# usbtinyisp.net
KiCad netlist of a schematic drawn in Altium Designer
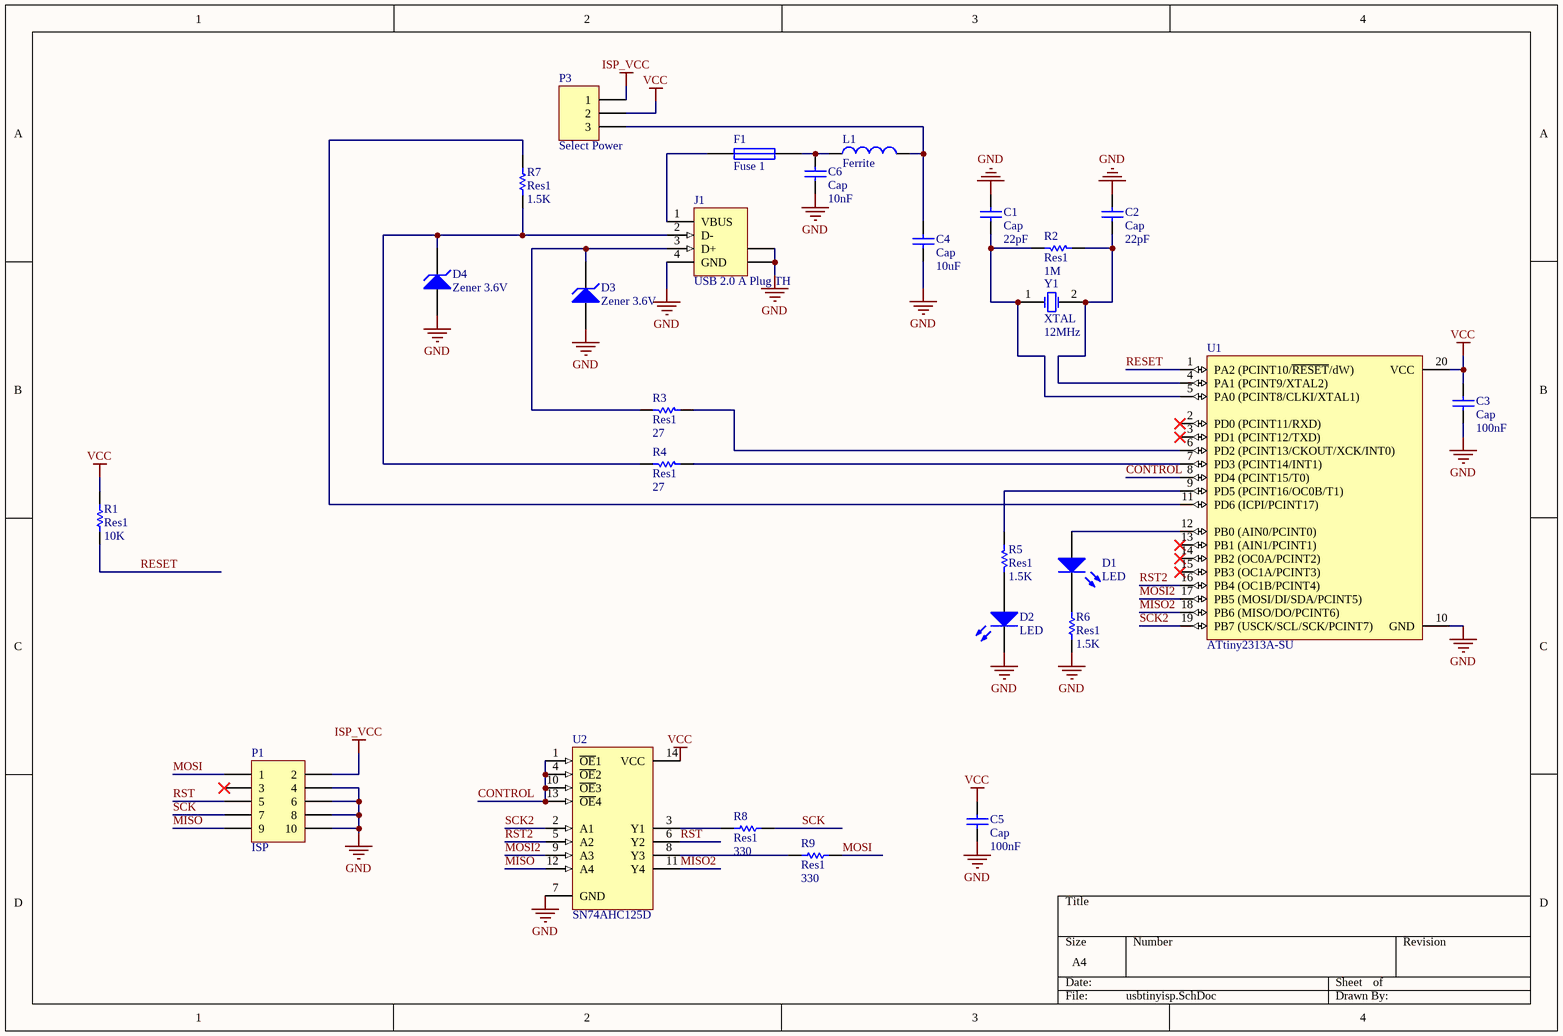
[diagram p0: usbtinyisp.SchDoc]

(export (version "E")
  (design (tool "Eeschema 10.0.6"))
  (components
    (comp (ref "C1")
      (value "Cap")
      (footprint "C0805")
      (description "Capacitor")
      (fields (field (name "ALTIUM_VALUE") "22pF") (field (name "PUBLISHER") "Altium Limited"))
      (libsource (lib "Miscellaneous Devices") (part "Cap"))
    )
    (comp (ref "C2")
      (value "Cap")
      (footprint "C0805")
      (description "Capacitor")
      (fields (field (name "ALTIUM_VALUE") "22pF") (field (name "PUBLISHER") "Altium Limited"))
      (libsource (lib "Miscellaneous Devices") (part "Cap"))
    )
    (comp (ref "C3")
      (value "Cap")
      (footprint "C0805")
      (description "Capacitor")
      (fields (field (name "ALTIUM_VALUE") "100nF") (field (name "PUBLISHER") "Altium Limited"))
      (libsource (lib "Miscellaneous Devices") (part "Cap"))
    )
    (comp (ref "C4")
      (value "Cap")
      (footprint "C0805")
      (description "Capacitor")
      (fields (field (name "ALTIUM_VALUE") "10uF") (field (name "PUBLISHER") "Altium Limited"))
      (libsource (lib "Miscellaneous Devices") (part "Cap"))
    )
    (comp (ref "C5")
      (value "Cap")
      (footprint "C0805")
      (description "Capacitor")
      (fields (field (name "ALTIUM_VALUE") "100nF") (field (name "PUBLISHER") "Altium Limited"))
      (libsource (lib "Miscellaneous Devices") (part "Cap"))
    )
    (comp (ref "C6")
      (value "Cap")
      (footprint "C0805")
      (description "Capacitor")
      (fields (field (name "ALTIUM_VALUE") "10nF") (field (name "PUBLISHER") "Altium Limited"))
      (libsource (lib "Miscellaneous Devices") (part "Cap"))
    )
    (comp (ref "D1")
      (value "LED")
      (footprint "C0805")
      (description "Typical RED GaAs LED")
      (fields (field (name "DESIGNER") "Meysam Parvizi") (field (name "EMAIL") "meysam.parvizi.ir@gmail.com"))
      (libsource (lib "mp") (part "LED"))
    )
    (comp (ref "D2")
      (value "LED")
      (footprint "C0805")
      (description "Typical RED GaAs LED")
      (fields (field (name "DESIGNER") "Meysam Parvizi") (field (name "EMAIL") "meysam.parvizi.ir@gmail.com"))
      (libsource (lib "mp") (part "LED"))
    )
    (comp (ref "D3")
      (value "Zener 3.6V")
      (footprint "DO-35")
      (description "Zener Diode")
      (fields (field (name "PUBLISHER") "Altium Limited"))
      (libsource (lib "Miscellaneous Devices") (part "D Zener"))
    )
    (comp (ref "D4")
      (value "Zener 3.6V")
      (footprint "DO-35")
      (description "Zener Diode")
      (fields (field (name "PUBLISHER") "Altium Limited"))
      (libsource (lib "Miscellaneous Devices") (part "D Zener"))
    )
    (comp (ref "F1")
      (value "Fuse 1")
      (footprint "C0805")
      (description "Fuse")
      (fields (field (name "PUBLISHER") "Altium Limited"))
      (libsource (lib "Miscellaneous Devices") (part "Fuse 1"))
    )
    (comp (ref "J1")
      (value "USB 2.0 A Plug TH")
      (footprint "USB2_A_TH_PLUG")
      (description "USB 2.0 A Plug, Thru-Hole")
      (libsource (lib "mp") (part "USB 2.0 A Plug TH"))
    )
    (comp (ref "L1")
      (value "Ferrite")
      (footprint "C0805")
      (description "Inductor")
      (fields (field (name "PUBLISHER") "Altium Limited"))
      (libsource (lib "Miscellaneous Devices") (part "Inductor"))
    )
    (comp (ref "P1")
      (value "ISP")
      (footprint "BOX2X5_PCB_EDGE")
      (description "Box, 5-Pin, Dual row")
      (fields (field (name "DESIGNER") "Meysam Parvizi") (field (name "EMAIL") "meysam.parvizi.ir@gmail.com"))
      (libsource (lib "mp") (part "Box 5X2"))
    )
    (comp (ref "P3")
      (value "Select Power")
      (footprint "HDR1X3")
      (description "Header, 3-Pin")
      (fields (field (name "PUBLISHER") "Altium Limited"))
      (libsource (lib "Miscellaneous Connectors") (part "Header 3"))
    )
    (comp (ref "R1")
      (value "Res1")
      (footprint "C0805")
      (description "Resistor")
      (fields (field (name "ALTIUM_VALUE") "10K") (field (name "PUBLISHER") "Altium Limited"))
      (libsource (lib "Miscellaneous Devices") (part "Res1"))
    )
    (comp (ref "R2")
      (value "Res1")
      (footprint "C0805")
      (description "Resistor")
      (fields (field (name "ALTIUM_VALUE") "1M") (field (name "PUBLISHER") "Altium Limited"))
      (libsource (lib "Miscellaneous Devices") (part "Res1"))
    )
    (comp (ref "R3")
      (value "Res1")
      (footprint "C0805")
      (description "Resistor")
      (fields (field (name "ALTIUM_VALUE") "27") (field (name "PUBLISHER") "Altium Limited"))
      (libsource (lib "Miscellaneous Devices") (part "Res1"))
    )
    (comp (ref "R4")
      (value "Res1")
      (footprint "C0805")
      (description "Resistor")
      (fields (field (name "ALTIUM_VALUE") "27") (field (name "PUBLISHER") "Altium Limited"))
      (libsource (lib "Miscellaneous Devices") (part "Res1"))
    )
    (comp (ref "R5")
      (value "Res1")
      (footprint "C0805")
      (description "Resistor")
      (fields (field (name "ALTIUM_VALUE") "1.5K") (field (name "PUBLISHER") "Altium Limited"))
      (libsource (lib "Miscellaneous Devices") (part "Res1"))
    )
    (comp (ref "R6")
      (value "Res1")
      (footprint "C0805")
      (description "Resistor")
      (fields (field (name "ALTIUM_VALUE") "1.5K") (field (name "PUBLISHER") "Altium Limited"))
      (libsource (lib "Miscellaneous Devices") (part "Res1"))
    )
    (comp (ref "R7")
      (value "Res1")
      (footprint "C0805")
      (description "Resistor")
      (fields (field (name "ALTIUM_VALUE") "1.5K") (field (name "PUBLISHER") "Altium Limited"))
      (libsource (lib "Miscellaneous Devices") (part "Res1"))
    )
    (comp (ref "R8")
      (value "Res1")
      (footprint "C0805")
      (description "Resistor")
      (fields (field (name "ALTIUM_VALUE") "330") (field (name "PUBLISHER") "Altium Limited"))
      (libsource (lib "Miscellaneous Devices") (part "Res1"))
    )
    (comp (ref "R9")
      (value "Res1")
      (footprint "C0805")
      (description "Resistor")
      (fields (field (name "ALTIUM_VALUE") "330") (field (name "PUBLISHER") "Altium Limited"))
      (libsource (lib "Miscellaneous Devices") (part "Res1"))
    )
    (comp (ref "U1")
      (value "ATtiny2313A-SU")
      (footprint "20S_M")
      (fields (field (name "PUBLISHER") "Altium Limited"))
      (libsource (lib "Atmel Microcontroller 8-Bit tinyAVR") (part "ATtiny2313A-SU"))
    )
    (comp (ref "U2")
      (value "SN74AHC125D")
      (footprint "D014_M")
      (description "Quadruple Bus Buffer Gate with 3-State Outputs")
      (fields (field (name "PUBLISHER") "Altium Limited"))
      (libsource (lib "TI Logic Buffer Line Driver") (part "SN74AHC125D"))
    )
    (comp (ref "Y1")
      (value "XTAL")
      (footprint "XTAL")
      (description "Crystal Oscillator")
      (fields
        (field (name "ALTIUM_VALUE") "12MHz")
        (field (name "DESIGNER") "Meysam Parvizi")
        (field (name "EMAIL") "meysam.parvizi.ir@gmail.com")
      )
      (libsource (lib "mp") (part "XTAL"))
    )
  )
  (nets
    (net (code "1") (name "/CONTROL") (class "Default")
      (node (ref "U1") (pin "8") (pinfunction "PD4_(PCINT15/T0)_8") (pintype "bidirectional"))
      (node (ref "U2") (pin "1") (pinfunction "~{OE}1_1") (pintype "input"))
      (node (ref "U2") (pin "10") (pinfunction "~{OE}3_10") (pintype "input"))
      (node (ref "U2") (pin "13") (pinfunction "~{OE}4_13") (pintype "input"))
      (node (ref "U2") (pin "4") (pinfunction "~{OE}2_4") (pintype "input"))
    )
    (net (code "2") (name "/MISO") (class "Default")
      (node (ref "P1") (pin "9") (pinfunction "9_9") (pintype "passive"))
      (node (ref "U2") (pin "12") (pinfunction "A4_12") (pintype "input"))
    )
    (net (code "3") (name "/MISO2") (class "Default")
      (node (ref "U1") (pin "18") (pinfunction "PB6_(MISO/DO/PCINT6)_18") (pintype "bidirectional"))
      (node (ref "U2") (pin "11") (pinfunction "Y4_11") (pintype "tri_state"))
    )
    (net (code "4") (name "/MOSI") (class "Default")
      (node (ref "P1") (pin "1") (pinfunction "1_1") (pintype "passive"))
      (node (ref "R9") (pin "2") (pinfunction "2_2") (pintype "passive"))
    )
    (net (code "5") (name "/MOSI2") (class "Default")
      (node (ref "U1") (pin "17") (pinfunction "PB5_(MOSI/DI/SDA/PCINT5)_17") (pintype "bidirectional"))
      (node (ref "U2") (pin "9") (pinfunction "A3_9") (pintype "input"))
    )
    (net (code "6") (name "/RESET") (class "Default")
      (node (ref "R1") (pin "1") (pinfunction "1_1") (pintype "passive"))
      (node (ref "U1") (pin "1") (pinfunction "PA2_(PCINT10/~{RESET}/dW)_1") (pintype "bidirectional"))
    )
    (net (code "7") (name "/RST") (class "Default")
      (node (ref "P1") (pin "5") (pinfunction "5_5") (pintype "passive"))
      (node (ref "U2") (pin "6") (pinfunction "Y2_6") (pintype "tri_state"))
    )
    (net (code "8") (name "/RST2") (class "Default")
      (node (ref "U1") (pin "16") (pinfunction "PB4_(OC1B/PCINT4)_16") (pintype "bidirectional"))
      (node (ref "U2") (pin "5") (pinfunction "A2_5") (pintype "input"))
    )
    (net (code "9") (name "/SCK") (class "Default")
      (node (ref "P1") (pin "7") (pinfunction "7_7") (pintype "passive"))
      (node (ref "R8") (pin "2") (pinfunction "2_2") (pintype "passive"))
    )
    (net (code "10") (name "/SCK2") (class "Default")
      (node (ref "U1") (pin "19") (pinfunction "PB7_(USCK/SCL/SCK/PCINT7)_19") (pintype "bidirectional"))
      (node (ref "U2") (pin "2") (pinfunction "A1_2") (pintype "input"))
    )
    (net (code "11") (name "GND") (class "Default")
      (node (ref "C1") (pin "1") (pinfunction "1_1") (pintype "passive"))
      (node (ref "C2") (pin "1") (pinfunction "1_1") (pintype "passive"))
      (node (ref "C3") (pin "1") (pinfunction "1_1") (pintype "passive"))
      (node (ref "C4") (pin "2") (pinfunction "2_2") (pintype "passive"))
      (node (ref "C5") (pin "1") (pinfunction "1_1") (pintype "passive"))
      (node (ref "C6") (pin "1") (pinfunction "1_1") (pintype "passive"))
      (node (ref "D2") (pin "2") (pinfunction "K_2") (pintype "passive"))
      (node (ref "D3") (pin "1") (pinfunction "A_1") (pintype "passive"))
      (node (ref "D4") (pin "1") (pinfunction "A_1") (pintype "passive"))
      (node (ref "J1") (pin "4") (pinfunction "GND_4") (pintype "power_in"))
      (node (ref "J1") (pin "5") (pinfunction "SHLD_5") (pintype "passive"))
      (node (ref "J1") (pin "6") (pinfunction "SHLD_6") (pintype "passive"))
      (node (ref "P1") (pin "10") (pinfunction "10_10") (pintype "passive"))
      (node (ref "P1") (pin "4") (pinfunction "4_4") (pintype "passive"))
      (node (ref "P1") (pin "6") (pinfunction "6_6") (pintype "passive"))
      (node (ref "P1") (pin "8") (pinfunction "8_8") (pintype "passive"))
      (node (ref "R6") (pin "2") (pinfunction "2_2") (pintype "passive"))
      (node (ref "U1") (pin "10") (pinfunction "GND_10") (pintype "power_in"))
      (node (ref "U2") (pin "7") (pinfunction "GND_7") (pintype "power_in"))
    )
    (net (code "12") (name "ISP_VCC") (class "Default")
      (node (ref "P1") (pin "2") (pinfunction "2_2") (pintype "passive"))
      (node (ref "P3") (pin "1") (pinfunction "1_1") (pintype "passive"))
    )
    (net (code "13") (name "Net-(C4-Pad1)") (class "Default")
      (node (ref "C4") (pin "1") (pinfunction "1_1") (pintype "passive"))
      (node (ref "L1") (pin "1") (pinfunction "1_1") (pintype "passive"))
      (node (ref "P3") (pin "3") (pinfunction "3_3") (pintype "passive"))
    )
    (net (code "14") (name "Net-(C6-Pad2)") (class "Default")
      (node (ref "C6") (pin "2") (pinfunction "2_2") (pintype "passive"))
      (node (ref "F1") (pin "1") (pinfunction "1_1") (pintype "passive"))
      (node (ref "L1") (pin "2") (pinfunction "2_2") (pintype "passive"))
    )
    (net (code "15") (name "Net-(D1-A)") (class "Default")
      (node (ref "D1") (pin "1") (pinfunction "A_1") (pintype "passive"))
      (node (ref "U1") (pin "12") (pinfunction "PB0_(AIN0/PCINT0)_12") (pintype "bidirectional"))
    )
    (net (code "16") (name "Net-(D1-K)") (class "Default")
      (node (ref "D1") (pin "2") (pinfunction "K_2") (pintype "passive"))
      (node (ref "R6") (pin "1") (pinfunction "1_1") (pintype "passive"))
    )
    (net (code "17") (name "Net-(D2-A)") (class "Default")
      (node (ref "D2") (pin "1") (pinfunction "A_1") (pintype "passive"))
      (node (ref "R5") (pin "2") (pinfunction "2_2") (pintype "passive"))
    )
    (net (code "18") (name "Net-(D3-K)") (class "Default")
      (node (ref "D3") (pin "2") (pinfunction "K_2") (pintype "passive"))
      (node (ref "J1") (pin "3") (pinfunction "D+_3") (pintype "input"))
      (node (ref "R3") (pin "1") (pinfunction "1_1") (pintype "passive"))
    )
    (net (code "19") (name "Net-(D4-K)") (class "Default")
      (node (ref "D4") (pin "2") (pinfunction "K_2") (pintype "passive"))
      (node (ref "J1") (pin "2") (pinfunction "D-_2") (pintype "input"))
      (node (ref "R4") (pin "1") (pinfunction "1_1") (pintype "passive"))
      (node (ref "R7") (pin "1") (pinfunction "1_1") (pintype "passive"))
    )
    (net (code "20") (name "Net-(J1-VBUS)") (class "Default")
      (node (ref "F1") (pin "2") (pinfunction "2_2") (pintype "passive"))
      (node (ref "J1") (pin "1") (pinfunction "VBUS_1") (pintype "power_in"))
    )
    (net (code "21") (name "Net-(U1-PA0_(PCINT8{slash}CLKI{slash}XTAL1))") (class "Default")
      (node (ref "C1") (pin "2") (pinfunction "2_2") (pintype "passive"))
      (node (ref "R2") (pin "2") (pinfunction "2_2") (pintype "passive"))
      (node (ref "U1") (pin "5") (pinfunction "PA0_(PCINT8/CLKI/XTAL1)_5") (pintype "bidirectional"))
      (node (ref "Y1") (pin "1") (pinfunction "OSC1_1") (pintype "passive"))
    )
    (net (code "22") (name "Net-(U1-PA1_(PCINT9{slash}XTAL2))") (class "Default")
      (node (ref "C2") (pin "2") (pinfunction "2_2") (pintype "passive"))
      (node (ref "R2") (pin "1") (pinfunction "1_1") (pintype "passive"))
      (node (ref "U1") (pin "4") (pinfunction "PA1_(PCINT9/XTAL2)_4") (pintype "bidirectional"))
      (node (ref "Y1") (pin "2") (pinfunction "OSC2_2") (pintype "passive"))
    )
    (net (code "23") (name "Net-(U1-PD2_(PCINT13{slash}CKOUT{slash}XCK{slash}INT0))") (class "Default")
      (node (ref "R3") (pin "2") (pinfunction "2_2") (pintype "passive"))
      (node (ref "U1") (pin "6") (pinfunction "PD2_(PCINT13/CKOUT/XCK/INT0)_6") (pintype "bidirectional"))
    )
    (net (code "24") (name "Net-(U1-PD3_(PCINT14{slash}INT1))") (class "Default")
      (node (ref "R4") (pin "2") (pinfunction "2_2") (pintype "passive"))
      (node (ref "U1") (pin "7") (pinfunction "PD3_(PCINT14/INT1)_7") (pintype "bidirectional"))
    )
    (net (code "25") (name "Net-(U1-PD5_(PCINT16{slash}OC0B{slash}T1))") (class "Default")
      (node (ref "R5") (pin "1") (pinfunction "1_1") (pintype "passive"))
      (node (ref "U1") (pin "9") (pinfunction "PD5_(PCINT16/OC0B/T1)_9") (pintype "bidirectional"))
    )
    (net (code "26") (name "Net-(U1-PD6_(ICPI{slash}PCINT17))") (class "Default")
      (node (ref "R7") (pin "2") (pinfunction "2_2") (pintype "passive"))
      (node (ref "U1") (pin "11") (pinfunction "PD6_(ICPI/PCINT17)_11") (pintype "bidirectional"))
    )
    (net (code "27") (name "Net-(U2-Y1)") (class "Default")
      (node (ref "R8") (pin "1") (pinfunction "1_1") (pintype "passive"))
      (node (ref "U2") (pin "3") (pinfunction "Y1_3") (pintype "tri_state"))
    )
    (net (code "28") (name "Net-(U2-Y3)") (class "Default")
      (node (ref "R9") (pin "1") (pinfunction "1_1") (pintype "passive"))
      (node (ref "U2") (pin "8") (pinfunction "Y3_8") (pintype "tri_state"))
    )
    (net (code "29") (name "VCC") (class "Default")
      (node (ref "C3") (pin "2") (pinfunction "2_2") (pintype "passive"))
      (node (ref "C5") (pin "2") (pinfunction "2_2") (pintype "passive"))
      (node (ref "P3") (pin "2") (pinfunction "2_2") (pintype "passive"))
      (node (ref "R1") (pin "2") (pinfunction "2_2") (pintype "passive"))
      (node (ref "U1") (pin "20") (pinfunction "VCC_20") (pintype "power_in"))
      (node (ref "U2") (pin "14") (pinfunction "VCC_14") (pintype "power_in"))
    )
    (net (code "30") (name "unconnected-(P1-Pad3)") (class "Default")
      (node (ref "P1") (pin "3") (pinfunction "3_3") (pintype "passive+no_connect"))
    )
    (net (code "31") (name "unconnected-(U1-PB1_(AIN1{slash}PCINT1)-Pad13)") (class "Default")
      (node (ref "U1") (pin "13") (pinfunction "PB1_(AIN1/PCINT1)_13") (pintype "bidirectional+no_connect"))
    )
    (net (code "32") (name "unconnected-(U1-PB2_(OC0A{slash}PCINT2)-Pad14)") (class "Default")
      (node (ref "U1") (pin "14") (pinfunction "PB2_(OC0A/PCINT2)_14") (pintype "bidirectional+no_connect"))
    )
    (net (code "33") (name "unconnected-(U1-PB3_(OC1A{slash}PCINT3)-Pad15)") (class "Default")
      (node (ref "U1") (pin "15") (pinfunction "PB3_(OC1A/PCINT3)_15") (pintype "bidirectional+no_connect"))
    )
    (net (code "34") (name "unconnected-(U1-PD0_(PCINT11{slash}RXD)-Pad2)") (class "Default")
      (node (ref "U1") (pin "2") (pinfunction "PD0_(PCINT11/RXD)_2") (pintype "bidirectional+no_connect"))
    )
    (net (code "35") (name "unconnected-(U1-PD1_(PCINT12{slash}TXD)-Pad3)") (class "Default")
      (node (ref "U1") (pin "3") (pinfunction "PD1_(PCINT12/TXD)_3") (pintype "bidirectional+no_connect"))
    )
  )
)
